# qfp160_socket.net
KiCad netlist of a schematic drawn in EAGLE
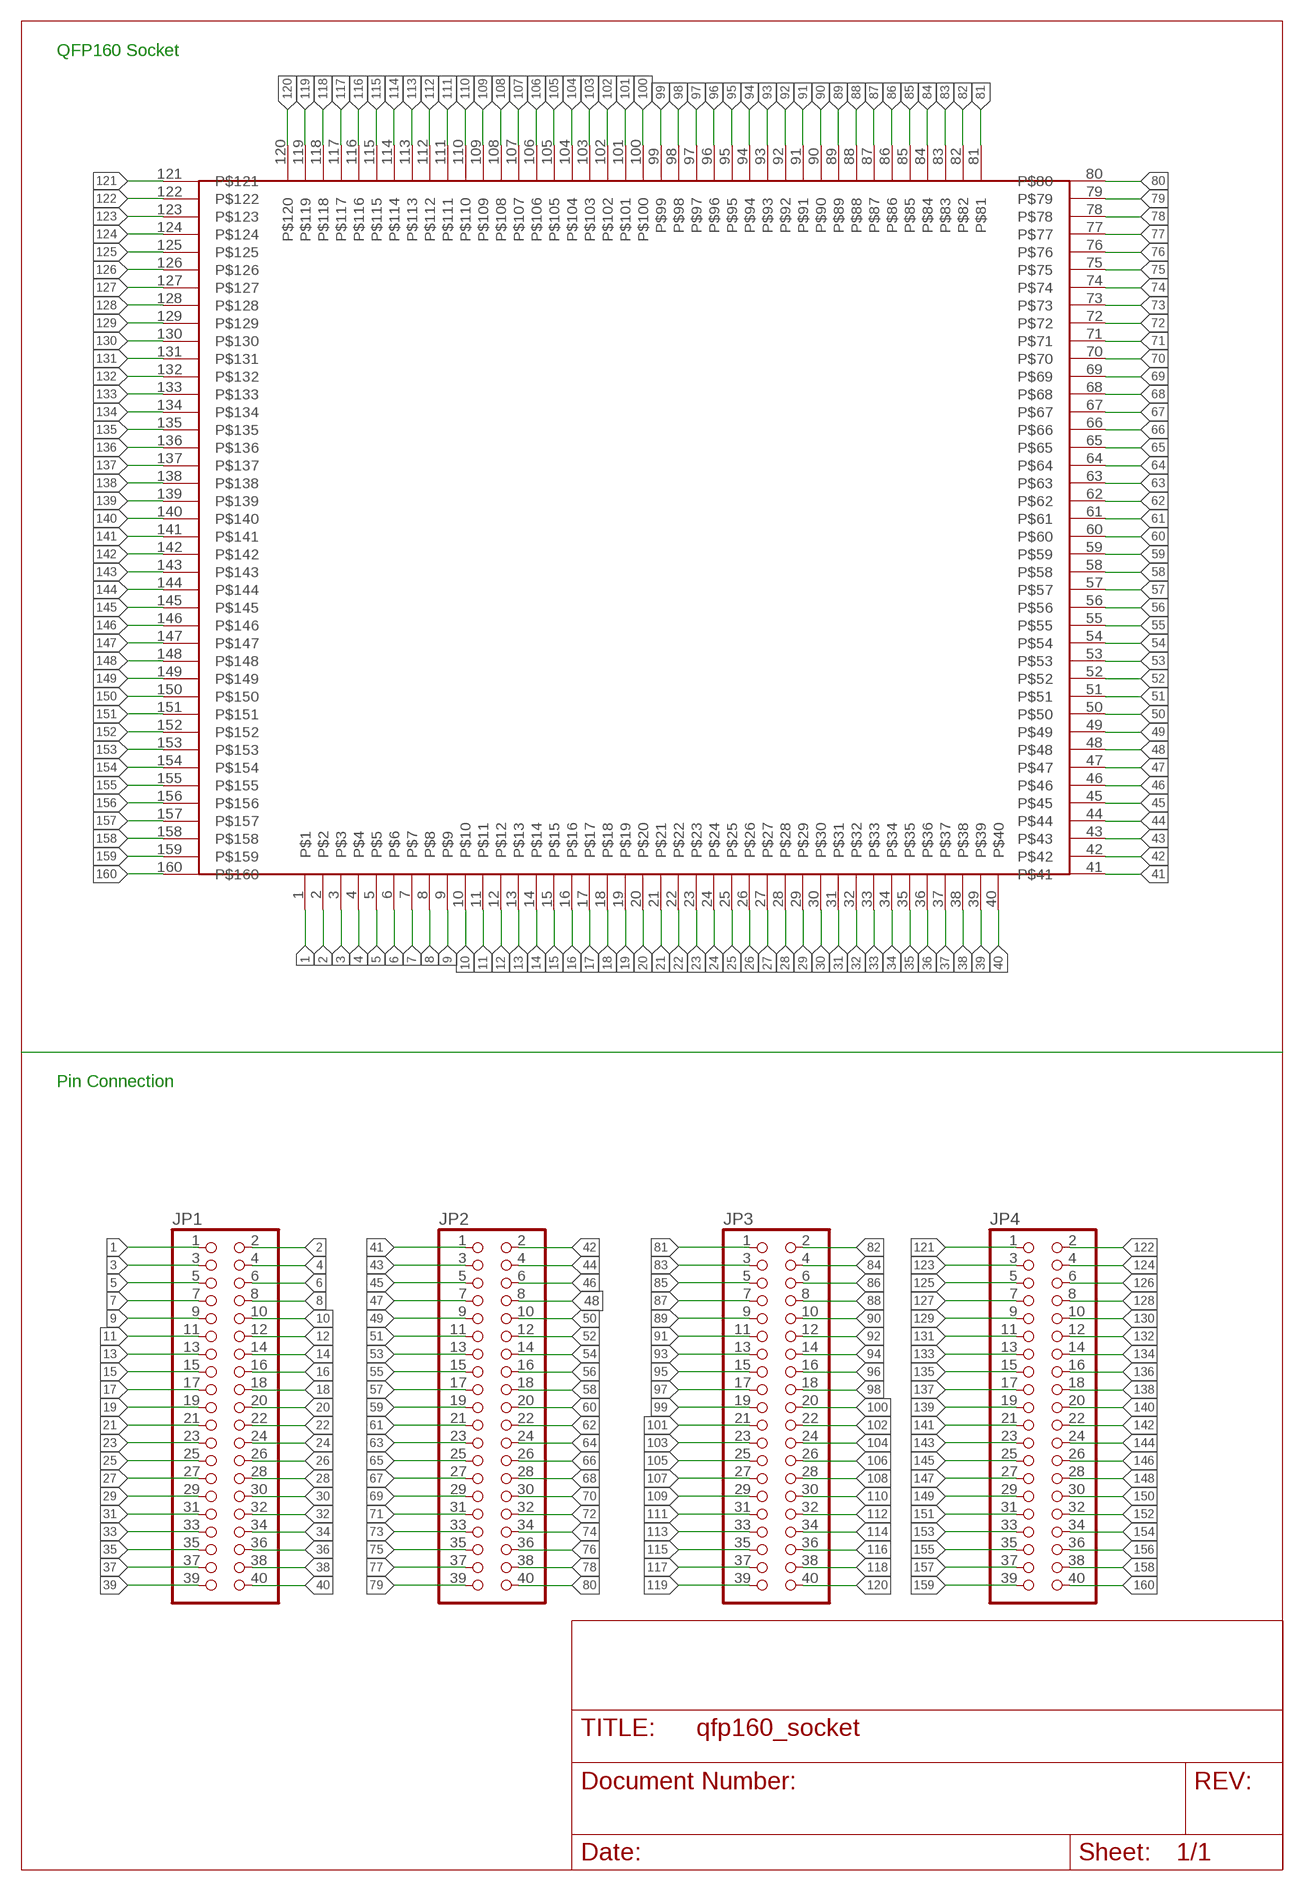
[diagram p0: schematic, sheet 1]

(export (version "E")
  (design (tool "Eeschema 10.0.6"))
  (components
    (comp (ref "JP1")
      (value "PINHD-2X20")
      (footprint "eagle-import:2X20")
      (libsource (lib "eagle-import") (part "PINHD-2X20"))
    )
    (comp (ref "JP2")
      (value "PINHD-2X20")
      (footprint "eagle-import:2X20")
      (libsource (lib "eagle-import") (part "PINHD-2X20"))
    )
    (comp (ref "JP3")
      (value "PINHD-2X20")
      (footprint "eagle-import:2X20")
      (libsource (lib "eagle-import") (part "PINHD-2X20"))
    )
    (comp (ref "JP4")
      (value "PINHD-2X20")
      (footprint "eagle-import:2X20")
      (libsource (lib "eagle-import") (part "PINHD-2X20"))
    )
    (comp (ref "U$1")
      (value "QFP160_SOCKET")
      (footprint "eagle-import:QFP160_SOCKET")
      (libsource (lib "eagle-import") (part "QFP160_SOCKET"))
    )
  )
  (nets
    (net (code "1") (name "1") (class "Default")
      (node (ref "JP1") (pin "1") (pinfunction "1_1") (pintype "passive"))
      (node (ref "U$1") (pin "1") (pinfunction "P$1_1") (pintype "bidirectional"))
    )
    (net (code "2") (name "2") (class "Default")
      (node (ref "JP1") (pin "2") (pinfunction "2_2") (pintype "passive"))
      (node (ref "U$1") (pin "2") (pinfunction "P$2_2") (pintype "bidirectional"))
    )
    (net (code "3") (name "3") (class "Default")
      (node (ref "JP1") (pin "3") (pinfunction "3_3") (pintype "passive"))
      (node (ref "U$1") (pin "3") (pinfunction "P$3_3") (pintype "bidirectional"))
    )
    (net (code "4") (name "4") (class "Default")
      (node (ref "JP1") (pin "4") (pinfunction "4_4") (pintype "passive"))
      (node (ref "U$1") (pin "4") (pinfunction "P$4_4") (pintype "bidirectional"))
    )
    (net (code "5") (name "5") (class "Default")
      (node (ref "JP1") (pin "5") (pinfunction "5_5") (pintype "passive"))
      (node (ref "U$1") (pin "5") (pinfunction "P$5_5") (pintype "bidirectional"))
    )
    (net (code "6") (name "6") (class "Default")
      (node (ref "JP1") (pin "6") (pinfunction "6_6") (pintype "passive"))
      (node (ref "U$1") (pin "6") (pinfunction "P$6_6") (pintype "bidirectional"))
    )
    (net (code "7") (name "7") (class "Default")
      (node (ref "JP1") (pin "7") (pinfunction "7_7") (pintype "passive"))
      (node (ref "U$1") (pin "7") (pinfunction "P$7_7") (pintype "bidirectional"))
    )
    (net (code "8") (name "8") (class "Default")
      (node (ref "JP1") (pin "8") (pinfunction "8_8") (pintype "passive"))
      (node (ref "U$1") (pin "8") (pinfunction "P$8_8") (pintype "bidirectional"))
    )
    (net (code "9") (name "9") (class "Default")
      (node (ref "JP1") (pin "9") (pinfunction "9_9") (pintype "passive"))
      (node (ref "U$1") (pin "9") (pinfunction "P$9_9") (pintype "bidirectional"))
    )
    (net (code "10") (name "10") (class "Default")
      (node (ref "JP1") (pin "10") (pinfunction "10_10") (pintype "passive"))
      (node (ref "U$1") (pin "10") (pinfunction "P$10_10") (pintype "bidirectional"))
    )
    (net (code "11") (name "11") (class "Default")
      (node (ref "JP1") (pin "11") (pinfunction "11_11") (pintype "passive"))
      (node (ref "U$1") (pin "11") (pinfunction "P$11_11") (pintype "bidirectional"))
    )
    (net (code "12") (name "12") (class "Default")
      (node (ref "JP1") (pin "12") (pinfunction "12_12") (pintype "passive"))
      (node (ref "U$1") (pin "12") (pinfunction "P$12_12") (pintype "bidirectional"))
    )
    (net (code "13") (name "13") (class "Default")
      (node (ref "JP1") (pin "13") (pinfunction "13_13") (pintype "passive"))
      (node (ref "U$1") (pin "13") (pinfunction "P$13_13") (pintype "bidirectional"))
    )
    (net (code "14") (name "14") (class "Default")
      (node (ref "JP1") (pin "14") (pinfunction "14_14") (pintype "passive"))
      (node (ref "U$1") (pin "14") (pinfunction "P$14_14") (pintype "bidirectional"))
    )
    (net (code "15") (name "15") (class "Default")
      (node (ref "JP1") (pin "15") (pinfunction "15_15") (pintype "passive"))
      (node (ref "U$1") (pin "15") (pinfunction "P$15_15") (pintype "bidirectional"))
    )
    (net (code "16") (name "16") (class "Default")
      (node (ref "JP1") (pin "16") (pinfunction "16_16") (pintype "passive"))
      (node (ref "U$1") (pin "16") (pinfunction "P$16_16") (pintype "bidirectional"))
    )
    (net (code "17") (name "17") (class "Default")
      (node (ref "JP1") (pin "17") (pinfunction "17_17") (pintype "passive"))
      (node (ref "U$1") (pin "17") (pinfunction "P$17_17") (pintype "bidirectional"))
    )
    (net (code "18") (name "18") (class "Default")
      (node (ref "JP1") (pin "18") (pinfunction "18_18") (pintype "passive"))
      (node (ref "U$1") (pin "18") (pinfunction "P$18_18") (pintype "bidirectional"))
    )
    (net (code "19") (name "19") (class "Default")
      (node (ref "JP1") (pin "19") (pinfunction "19_19") (pintype "passive"))
      (node (ref "U$1") (pin "19") (pinfunction "P$19_19") (pintype "bidirectional"))
    )
    (net (code "20") (name "20") (class "Default")
      (node (ref "JP1") (pin "20") (pinfunction "20_20") (pintype "passive"))
      (node (ref "U$1") (pin "20") (pinfunction "P$20_20") (pintype "bidirectional"))
    )
    (net (code "21") (name "21") (class "Default")
      (node (ref "JP1") (pin "21") (pinfunction "21_21") (pintype "passive"))
      (node (ref "U$1") (pin "21") (pinfunction "P$21_21") (pintype "bidirectional"))
    )
    (net (code "22") (name "22") (class "Default")
      (node (ref "JP1") (pin "22") (pinfunction "22_22") (pintype "passive"))
      (node (ref "U$1") (pin "22") (pinfunction "P$22_22") (pintype "bidirectional"))
    )
    (net (code "23") (name "23") (class "Default")
      (node (ref "JP1") (pin "23") (pinfunction "23_23") (pintype "passive"))
      (node (ref "U$1") (pin "23") (pinfunction "P$23_23") (pintype "bidirectional"))
    )
    (net (code "24") (name "24") (class "Default")
      (node (ref "JP1") (pin "24") (pinfunction "24_24") (pintype "passive"))
      (node (ref "U$1") (pin "24") (pinfunction "P$24_24") (pintype "bidirectional"))
    )
    (net (code "25") (name "25") (class "Default")
      (node (ref "JP1") (pin "25") (pinfunction "25_25") (pintype "passive"))
      (node (ref "U$1") (pin "25") (pinfunction "P$25_25") (pintype "bidirectional"))
    )
    (net (code "26") (name "26") (class "Default")
      (node (ref "JP1") (pin "26") (pinfunction "26_26") (pintype "passive"))
      (node (ref "U$1") (pin "26") (pinfunction "P$26_26") (pintype "bidirectional"))
    )
    (net (code "27") (name "27") (class "Default")
      (node (ref "JP1") (pin "27") (pinfunction "27_27") (pintype "passive"))
      (node (ref "U$1") (pin "27") (pinfunction "P$27_27") (pintype "bidirectional"))
    )
    (net (code "28") (name "28") (class "Default")
      (node (ref "JP1") (pin "28") (pinfunction "28_28") (pintype "passive"))
      (node (ref "U$1") (pin "28") (pinfunction "P$28_28") (pintype "bidirectional"))
    )
    (net (code "29") (name "29") (class "Default")
      (node (ref "JP1") (pin "29") (pinfunction "29_29") (pintype "passive"))
      (node (ref "U$1") (pin "29") (pinfunction "P$29_29") (pintype "bidirectional"))
    )
    (net (code "30") (name "30") (class "Default")
      (node (ref "JP1") (pin "30") (pinfunction "30_30") (pintype "passive"))
      (node (ref "U$1") (pin "30") (pinfunction "P$30_30") (pintype "bidirectional"))
    )
    (net (code "31") (name "31") (class "Default")
      (node (ref "JP1") (pin "31") (pinfunction "31_31") (pintype "passive"))
      (node (ref "U$1") (pin "31") (pinfunction "P$31_31") (pintype "bidirectional"))
    )
    (net (code "32") (name "32") (class "Default")
      (node (ref "JP1") (pin "32") (pinfunction "32_32") (pintype "passive"))
      (node (ref "U$1") (pin "32") (pinfunction "P$32_32") (pintype "bidirectional"))
    )
    (net (code "33") (name "33") (class "Default")
      (node (ref "JP1") (pin "33") (pinfunction "33_33") (pintype "passive"))
      (node (ref "U$1") (pin "33") (pinfunction "P$33_33") (pintype "bidirectional"))
    )
    (net (code "34") (name "34") (class "Default")
      (node (ref "JP1") (pin "34") (pinfunction "34_34") (pintype "passive"))
      (node (ref "U$1") (pin "34") (pinfunction "P$34_34") (pintype "bidirectional"))
    )
    (net (code "35") (name "35") (class "Default")
      (node (ref "JP1") (pin "35") (pinfunction "35_35") (pintype "passive"))
      (node (ref "U$1") (pin "35") (pinfunction "P$35_35") (pintype "bidirectional"))
    )
    (net (code "36") (name "36") (class "Default")
      (node (ref "JP1") (pin "36") (pinfunction "36_36") (pintype "passive"))
      (node (ref "U$1") (pin "36") (pinfunction "P$36_36") (pintype "bidirectional"))
    )
    (net (code "37") (name "37") (class "Default")
      (node (ref "JP1") (pin "37") (pinfunction "37_37") (pintype "passive"))
      (node (ref "U$1") (pin "37") (pinfunction "P$37_37") (pintype "bidirectional"))
    )
    (net (code "38") (name "38") (class "Default")
      (node (ref "JP1") (pin "38") (pinfunction "38_38") (pintype "passive"))
      (node (ref "U$1") (pin "38") (pinfunction "P$38_38") (pintype "bidirectional"))
    )
    (net (code "39") (name "39") (class "Default")
      (node (ref "JP1") (pin "39") (pinfunction "39_39") (pintype "passive"))
      (node (ref "U$1") (pin "39") (pinfunction "P$39_39") (pintype "bidirectional"))
    )
    (net (code "40") (name "40") (class "Default")
      (node (ref "JP1") (pin "40") (pinfunction "40_40") (pintype "passive"))
      (node (ref "U$1") (pin "40") (pinfunction "P$40_40") (pintype "bidirectional"))
    )
    (net (code "41") (name "41") (class "Default")
      (node (ref "JP2") (pin "1") (pinfunction "1_1") (pintype "passive"))
      (node (ref "U$1") (pin "41") (pinfunction "P$41_41") (pintype "bidirectional"))
    )
    (net (code "42") (name "42") (class "Default")
      (node (ref "JP2") (pin "2") (pinfunction "2_2") (pintype "passive"))
      (node (ref "U$1") (pin "42") (pinfunction "P$42_42") (pintype "bidirectional"))
    )
    (net (code "43") (name "43") (class "Default")
      (node (ref "JP2") (pin "3") (pinfunction "3_3") (pintype "passive"))
      (node (ref "U$1") (pin "43") (pinfunction "P$43_43") (pintype "bidirectional"))
    )
    (net (code "44") (name "44") (class "Default")
      (node (ref "JP2") (pin "4") (pinfunction "4_4") (pintype "passive"))
      (node (ref "U$1") (pin "44") (pinfunction "P$44_44") (pintype "bidirectional"))
    )
    (net (code "45") (name "45") (class "Default")
      (node (ref "JP2") (pin "5") (pinfunction "5_5") (pintype "passive"))
      (node (ref "U$1") (pin "45") (pinfunction "P$45_45") (pintype "bidirectional"))
    )
    (net (code "46") (name "46") (class "Default")
      (node (ref "JP2") (pin "6") (pinfunction "6_6") (pintype "passive"))
      (node (ref "U$1") (pin "46") (pinfunction "P$46_46") (pintype "bidirectional"))
    )
    (net (code "47") (name "47") (class "Default")
      (node (ref "JP2") (pin "7") (pinfunction "7_7") (pintype "passive"))
      (node (ref "U$1") (pin "47") (pinfunction "P$47_47") (pintype "bidirectional"))
    )
    (net (code "48") (name "48") (class "Default")
      (node (ref "JP2") (pin "8") (pinfunction "8_8") (pintype "passive"))
      (node (ref "U$1") (pin "48") (pinfunction "P$48_48") (pintype "bidirectional"))
    )
    (net (code "49") (name "49") (class "Default")
      (node (ref "JP2") (pin "9") (pinfunction "9_9") (pintype "passive"))
      (node (ref "U$1") (pin "49") (pinfunction "P$49_49") (pintype "bidirectional"))
    )
    (net (code "50") (name "50") (class "Default")
      (node (ref "JP2") (pin "10") (pinfunction "10_10") (pintype "passive"))
      (node (ref "U$1") (pin "50") (pinfunction "P$50_50") (pintype "bidirectional"))
    )
    (net (code "51") (name "51") (class "Default")
      (node (ref "JP2") (pin "11") (pinfunction "11_11") (pintype "passive"))
      (node (ref "U$1") (pin "51") (pinfunction "P$51_51") (pintype "bidirectional"))
    )
    (net (code "52") (name "52") (class "Default")
      (node (ref "JP2") (pin "12") (pinfunction "12_12") (pintype "passive"))
      (node (ref "U$1") (pin "52") (pinfunction "P$52_52") (pintype "bidirectional"))
    )
    (net (code "53") (name "53") (class "Default")
      (node (ref "JP2") (pin "13") (pinfunction "13_13") (pintype "passive"))
      (node (ref "U$1") (pin "53") (pinfunction "P$53_53") (pintype "bidirectional"))
    )
    (net (code "54") (name "54") (class "Default")
      (node (ref "JP2") (pin "14") (pinfunction "14_14") (pintype "passive"))
      (node (ref "U$1") (pin "54") (pinfunction "P$54_54") (pintype "bidirectional"))
    )
    (net (code "55") (name "55") (class "Default")
      (node (ref "JP2") (pin "15") (pinfunction "15_15") (pintype "passive"))
      (node (ref "U$1") (pin "55") (pinfunction "P$55_55") (pintype "bidirectional"))
    )
    (net (code "56") (name "56") (class "Default")
      (node (ref "JP2") (pin "16") (pinfunction "16_16") (pintype "passive"))
      (node (ref "U$1") (pin "56") (pinfunction "P$56_56") (pintype "bidirectional"))
    )
    (net (code "57") (name "57") (class "Default")
      (node (ref "JP2") (pin "17") (pinfunction "17_17") (pintype "passive"))
      (node (ref "U$1") (pin "57") (pinfunction "P$57_57") (pintype "bidirectional"))
    )
    (net (code "58") (name "58") (class "Default")
      (node (ref "JP2") (pin "18") (pinfunction "18_18") (pintype "passive"))
      (node (ref "U$1") (pin "58") (pinfunction "P$58_58") (pintype "bidirectional"))
    )
    (net (code "59") (name "59") (class "Default")
      (node (ref "JP2") (pin "19") (pinfunction "19_19") (pintype "passive"))
      (node (ref "U$1") (pin "59") (pinfunction "P$59_59") (pintype "bidirectional"))
    )
    (net (code "60") (name "60") (class "Default")
      (node (ref "JP2") (pin "20") (pinfunction "20_20") (pintype "passive"))
      (node (ref "U$1") (pin "60") (pinfunction "P$60_60") (pintype "bidirectional"))
    )
    (net (code "61") (name "61") (class "Default")
      (node (ref "JP2") (pin "21") (pinfunction "21_21") (pintype "passive"))
      (node (ref "U$1") (pin "61") (pinfunction "P$61_61") (pintype "bidirectional"))
    )
    (net (code "62") (name "62") (class "Default")
      (node (ref "JP2") (pin "22") (pinfunction "22_22") (pintype "passive"))
      (node (ref "U$1") (pin "62") (pinfunction "P$62_62") (pintype "bidirectional"))
    )
    (net (code "63") (name "63") (class "Default")
      (node (ref "JP2") (pin "23") (pinfunction "23_23") (pintype "passive"))
      (node (ref "U$1") (pin "63") (pinfunction "P$63_63") (pintype "bidirectional"))
    )
    (net (code "64") (name "64") (class "Default")
      (node (ref "JP2") (pin "24") (pinfunction "24_24") (pintype "passive"))
      (node (ref "U$1") (pin "64") (pinfunction "P$64_64") (pintype "bidirectional"))
    )
    (net (code "65") (name "65") (class "Default")
      (node (ref "JP2") (pin "25") (pinfunction "25_25") (pintype "passive"))
      (node (ref "U$1") (pin "65") (pinfunction "P$65_65") (pintype "bidirectional"))
    )
    (net (code "66") (name "66") (class "Default")
      (node (ref "JP2") (pin "26") (pinfunction "26_26") (pintype "passive"))
      (node (ref "U$1") (pin "66") (pinfunction "P$66_66") (pintype "bidirectional"))
    )
    (net (code "67") (name "67") (class "Default")
      (node (ref "JP2") (pin "27") (pinfunction "27_27") (pintype "passive"))
      (node (ref "U$1") (pin "67") (pinfunction "P$67_67") (pintype "bidirectional"))
    )
    (net (code "68") (name "68") (class "Default")
      (node (ref "JP2") (pin "28") (pinfunction "28_28") (pintype "passive"))
      (node (ref "U$1") (pin "68") (pinfunction "P$68_68") (pintype "bidirectional"))
    )
    (net (code "69") (name "69") (class "Default")
      (node (ref "JP2") (pin "29") (pinfunction "29_29") (pintype "passive"))
      (node (ref "U$1") (pin "69") (pinfunction "P$69_69") (pintype "bidirectional"))
    )
    (net (code "70") (name "70") (class "Default")
      (node (ref "JP2") (pin "30") (pinfunction "30_30") (pintype "passive"))
      (node (ref "U$1") (pin "70") (pinfunction "P$70_70") (pintype "bidirectional"))
    )
    (net (code "71") (name "71") (class "Default")
      (node (ref "JP2") (pin "31") (pinfunction "31_31") (pintype "passive"))
      (node (ref "U$1") (pin "71") (pinfunction "P$71_71") (pintype "bidirectional"))
    )
    (net (code "72") (name "72") (class "Default")
      (node (ref "JP2") (pin "32") (pinfunction "32_32") (pintype "passive"))
      (node (ref "U$1") (pin "72") (pinfunction "P$72_72") (pintype "bidirectional"))
    )
    (net (code "73") (name "73") (class "Default")
      (node (ref "JP2") (pin "33") (pinfunction "33_33") (pintype "passive"))
      (node (ref "U$1") (pin "73") (pinfunction "P$73_73") (pintype "bidirectional"))
    )
    (net (code "74") (name "74") (class "Default")
      (node (ref "JP2") (pin "34") (pinfunction "34_34") (pintype "passive"))
      (node (ref "U$1") (pin "74") (pinfunction "P$74_74") (pintype "bidirectional"))
    )
    (net (code "75") (name "75") (class "Default")
      (node (ref "JP2") (pin "35") (pinfunction "35_35") (pintype "passive"))
      (node (ref "U$1") (pin "75") (pinfunction "P$75_75") (pintype "bidirectional"))
    )
    (net (code "76") (name "76") (class "Default")
      (node (ref "JP2") (pin "36") (pinfunction "36_36") (pintype "passive"))
      (node (ref "U$1") (pin "76") (pinfunction "P$76_76") (pintype "bidirectional"))
    )
    (net (code "77") (name "77") (class "Default")
      (node (ref "JP2") (pin "37") (pinfunction "37_37") (pintype "passive"))
      (node (ref "U$1") (pin "77") (pinfunction "P$77_77") (pintype "bidirectional"))
    )
    (net (code "78") (name "78") (class "Default")
      (node (ref "JP2") (pin "38") (pinfunction "38_38") (pintype "passive"))
      (node (ref "U$1") (pin "78") (pinfunction "P$78_78") (pintype "bidirectional"))
    )
    (net (code "79") (name "79") (class "Default")
      (node (ref "JP2") (pin "39") (pinfunction "39_39") (pintype "passive"))
      (node (ref "U$1") (pin "79") (pinfunction "P$79_79") (pintype "bidirectional"))
    )
    (net (code "80") (name "80") (class "Default")
      (node (ref "JP2") (pin "40") (pinfunction "40_40") (pintype "passive"))
      (node (ref "U$1") (pin "80") (pinfunction "P$80_80") (pintype "bidirectional"))
    )
    (net (code "81") (name "81") (class "Default")
      (node (ref "JP3") (pin "1") (pinfunction "1_1") (pintype "passive"))
      (node (ref "U$1") (pin "81") (pinfunction "P$81_81") (pintype "bidirectional"))
    )
    (net (code "82") (name "82") (class "Default")
      (node (ref "JP3") (pin "2") (pinfunction "2_2") (pintype "passive"))
      (node (ref "U$1") (pin "82") (pinfunction "P$82_82") (pintype "bidirectional"))
    )
    (net (code "83") (name "83") (class "Default")
      (node (ref "JP3") (pin "3") (pinfunction "3_3") (pintype "passive"))
      (node (ref "U$1") (pin "83") (pinfunction "P$83_83") (pintype "bidirectional"))
    )
    (net (code "84") (name "84") (class "Default")
      (node (ref "JP3") (pin "4") (pinfunction "4_4") (pintype "passive"))
      (node (ref "U$1") (pin "84") (pinfunction "P$84_84") (pintype "bidirectional"))
    )
    (net (code "85") (name "85") (class "Default")
      (node (ref "JP3") (pin "5") (pinfunction "5_5") (pintype "passive"))
      (node (ref "U$1") (pin "85") (pinfunction "P$85_85") (pintype "bidirectional"))
    )
    (net (code "86") (name "86") (class "Default")
      (node (ref "JP3") (pin "6") (pinfunction "6_6") (pintype "passive"))
      (node (ref "U$1") (pin "86") (pinfunction "P$86_86") (pintype "bidirectional"))
    )
    (net (code "87") (name "87") (class "Default")
      (node (ref "JP3") (pin "7") (pinfunction "7_7") (pintype "passive"))
      (node (ref "U$1") (pin "87") (pinfunction "P$87_87") (pintype "bidirectional"))
    )
    (net (code "88") (name "88") (class "Default")
      (node (ref "JP3") (pin "8") (pinfunction "8_8") (pintype "passive"))
      (node (ref "U$1") (pin "88") (pinfunction "P$88_88") (pintype "bidirectional"))
    )
    (net (code "89") (name "89") (class "Default")
      (node (ref "JP3") (pin "9") (pinfunction "9_9") (pintype "passive"))
      (node (ref "U$1") (pin "89") (pinfunction "P$89_89") (pintype "bidirectional"))
    )
    (net (code "90") (name "90") (class "Default")
      (node (ref "JP3") (pin "10") (pinfunction "10_10") (pintype "passive"))
      (node (ref "U$1") (pin "90") (pinfunction "P$90_90") (pintype "bidirectional"))
    )
    (net (code "91") (name "91") (class "Default")
      (node (ref "JP3") (pin "11") (pinfunction "11_11") (pintype "passive"))
      (node (ref "U$1") (pin "91") (pinfunction "P$91_91") (pintype "bidirectional"))
    )
    (net (code "92") (name "92") (class "Default")
      (node (ref "JP3") (pin "12") (pinfunction "12_12") (pintype "passive"))
      (node (ref "U$1") (pin "92") (pinfunction "P$92_92") (pintype "bidirectional"))
    )
    (net (code "93") (name "93") (class "Default")
      (node (ref "JP3") (pin "13") (pinfunction "13_13") (pintype "passive"))
      (node (ref "U$1") (pin "93") (pinfunction "P$93_93") (pintype "bidirectional"))
    )
    (net (code "94") (name "94") (class "Default")
      (node (ref "JP3") (pin "14") (pinfunction "14_14") (pintype "passive"))
      (node (ref "U$1") (pin "94") (pinfunction "P$94_94") (pintype "bidirectional"))
    )
    (net (code "95") (name "95") (class "Default")
      (node (ref "JP3") (pin "15") (pinfunction "15_15") (pintype "passive"))
      (node (ref "U$1") (pin "95") (pinfunction "P$95_95") (pintype "bidirectional"))
    )
    (net (code "96") (name "96") (class "Default")
      (node (ref "JP3") (pin "16") (pinfunction "16_16") (pintype "passive"))
      (node (ref "U$1") (pin "96") (pinfunction "P$96_96") (pintype "bidirectional"))
    )
    (net (code "97") (name "97") (class "Default")
      (node (ref "JP3") (pin "17") (pinfunction "17_17") (pintype "passive"))
      (node (ref "U$1") (pin "97") (pinfunction "P$97_97") (pintype "bidirectional"))
    )
    (net (code "98") (name "98") (class "Default")
      (node (ref "JP3") (pin "18") (pinfunction "18_18") (pintype "passive"))
      (node (ref "U$1") (pin "98") (pinfunction "P$98_98") (pintype "bidirectional"))
    )
    (net (code "99") (name "99") (class "Default")
      (node (ref "JP3") (pin "19") (pinfunction "19_19") (pintype "passive"))
      (node (ref "U$1") (pin "99") (pinfunction "P$99_99") (pintype "bidirectional"))
    )
    (net (code "100") (name "100") (class "Default")
      (node (ref "JP3") (pin "20") (pinfunction "20_20") (pintype "passive"))
      (node (ref "U$1") (pin "100") (pinfunction "P$100_100") (pintype "bidirectional"))
    )
    (net (code "101") (name "101") (class "Default")
      (node (ref "JP3") (pin "21") (pinfunction "21_21") (pintype "passive"))
      (node (ref "U$1") (pin "101") (pinfunction "P$101_101") (pintype "bidirectional"))
    )
    (net (code "102") (name "102") (class "Default")
      (node (ref "JP3") (pin "22") (pinfunction "22_22") (pintype "passive"))
      (node (ref "U$1") (pin "102") (pinfunction "P$102_102") (pintype "bidirectional"))
    )
    (net (code "103") (name "103") (class "Default")
      (node (ref "JP3") (pin "23") (pinfunction "23_23") (pintype "passive"))
      (node (ref "U$1") (pin "103") (pinfunction "P$103_103") (pintype "bidirectional"))
    )
    (net (code "104") (name "104") (class "Default")
      (node (ref "JP3") (pin "24") (pinfunction "24_24") (pintype "passive"))
      (node (ref "U$1") (pin "104") (pinfunction "P$104_104") (pintype "bidirectional"))
    )
    (net (code "105") (name "105") (class "Default")
      (node (ref "JP3") (pin "25") (pinfunction "25_25") (pintype "passive"))
      (node (ref "U$1") (pin "105") (pinfunction "P$105_105") (pintype "bidirectional"))
    )
    (net (code "106") (name "106") (class "Default")
      (node (ref "JP3") (pin "26") (pinfunction "26_26") (pintype "passive"))
      (node (ref "U$1") (pin "106") (pinfunction "P$106_106") (pintype "bidirectional"))
    )
    (net (code "107") (name "107") (class "Default")
      (node (ref "JP3") (pin "27") (pinfunction "27_27") (pintype "passive"))
      (node (ref "U$1") (pin "107") (pinfunction "P$107_107") (pintype "bidirectional"))
    )
    (net (code "108") (name "108") (class "Default")
      (node (ref "JP3") (pin "28") (pinfunction "28_28") (pintype "passive"))
      (node (ref "U$1") (pin "108") (pinfunction "P$108_108") (pintype "bidirectional"))
    )
    (net (code "109") (name "109") (class "Default")
      (node (ref "JP3") (pin "29") (pinfunction "29_29") (pintype "passive"))
      (node (ref "U$1") (pin "109") (pinfunction "P$109_109") (pintype "bidirectional"))
    )
    (net (code "110") (name "110") (class "Default")
      (node (ref "JP3") (pin "30") (pinfunction "30_30") (pintype "passive"))
      (node (ref "U$1") (pin "110") (pinfunction "P$110_110") (pintype "bidirectional"))
    )
    (net (code "111") (name "111") (class "Default")
      (node (ref "JP3") (pin "31") (pinfunction "31_31") (pintype "passive"))
      (node (ref "U$1") (pin "111") (pinfunction "P$111_111") (pintype "bidirectional"))
    )
    (net (code "112") (name "112") (class "Default")
      (node (ref "JP3") (pin "32") (pinfunction "32_32") (pintype "passive"))
      (node (ref "U$1") (pin "112") (pinfunction "P$112_112") (pintype "bidirectional"))
    )
    (net (code "113") (name "113") (class "Default")
      (node (ref "JP3") (pin "33") (pinfunction "33_33") (pintype "passive"))
      (node (ref "U$1") (pin "113") (pinfunction "P$113_113") (pintype "bidirectional"))
    )
    (net (code "114") (name "114") (class "Default")
      (node (ref "JP3") (pin "34") (pinfunction "34_34") (pintype "passive"))
      (node (ref "U$1") (pin "114") (pinfunction "P$114_114") (pintype "bidirectional"))
    )
    (net (code "115") (name "115") (class "Default")
      (node (ref "JP3") (pin "35") (pinfunction "35_35") (pintype "passive"))
      (node (ref "U$1") (pin "115") (pinfunction "P$115_115") (pintype "bidirectional"))
    )
    (net (code "116") (name "116") (class "Default")
      (node (ref "JP3") (pin "36") (pinfunction "36_36") (pintype "passive"))
      (node (ref "U$1") (pin "116") (pinfunction "P$116_116") (pintype "bidirectional"))
    )
    (net (code "117") (name "117") (class "Default")
      (node (ref "JP3") (pin "37") (pinfunction "37_37") (pintype "passive"))
      (node (ref "U$1") (pin "117") (pinfunction "P$117_117") (pintype "bidirectional"))
    )
    (net (code "118") (name "118") (class "Default")
      (node (ref "JP3") (pin "38") (pinfunction "38_38") (pintype "passive"))
      (node (ref "U$1") (pin "118") (pinfunction "P$118_118") (pintype "bidirectional"))
    )
    (net (code "119") (name "119") (class "Default")
      (node (ref "JP3") (pin "39") (pinfunction "39_39") (pintype "passive"))
      (node (ref "U$1") (pin "119") (pinfunction "P$119_119") (pintype "bidirectional"))
    )
    (net (code "120") (name "120") (class "Default")
      (node (ref "JP3") (pin "40") (pinfunction "40_40") (pintype "passive"))
      (node (ref "U$1") (pin "120") (pinfunction "P$120_120") (pintype "bidirectional"))
    )
    (net (code "121") (name "121") (class "Default")
      (node (ref "JP4") (pin "1") (pinfunction "1_1") (pintype "passive"))
      (node (ref "U$1") (pin "121") (pinfunction "P$121_121") (pintype "bidirectional"))
    )
    (net (code "122") (name "122") (class "Default")
      (node (ref "JP4") (pin "2") (pinfunction "2_2") (pintype "passive"))
      (node (ref "U$1") (pin "122") (pinfunction "P$122_122") (pintype "bidirectional"))
    )
    (net (code "123") (name "123") (class "Default")
      (node (ref "JP4") (pin "3") (pinfunction "3_3") (pintype "passive"))
      (node (ref "U$1") (pin "123") (pinfunction "P$123_123") (pintype "bidirectional"))
    )
    (net (code "124") (name "124") (class "Default")
      (node (ref "JP4") (pin "4") (pinfunction "4_4") (pintype "passive"))
      (node (ref "U$1") (pin "124") (pinfunction "P$124_124") (pintype "bidirectional"))
    )
    (net (code "125") (name "125") (class "Default")
      (node (ref "JP4") (pin "5") (pinfunction "5_5") (pintype "passive"))
      (node (ref "U$1") (pin "125") (pinfunction "P$125_125") (pintype "bidirectional"))
    )
    (net (code "126") (name "126") (class "Default")
      (node (ref "JP4") (pin "6") (pinfunction "6_6") (pintype "passive"))
      (node (ref "U$1") (pin "126") (pinfunction "P$126_126") (pintype "bidirectional"))
    )
    (net (code "127") (name "127") (class "Default")
      (node (ref "JP4") (pin "7") (pinfunction "7_7") (pintype "passive"))
      (node (ref "U$1") (pin "127") (pinfunction "P$127_127") (pintype "bidirectional"))
    )
    (net (code "128") (name "128") (class "Default")
      (node (ref "JP4") (pin "8") (pinfunction "8_8") (pintype "passive"))
      (node (ref "U$1") (pin "128") (pinfunction "P$128_128") (pintype "bidirectional"))
    )
    (net (code "129") (name "129") (class "Default")
      (node (ref "JP4") (pin "9") (pinfunction "9_9") (pintype "passive"))
      (node (ref "U$1") (pin "129") (pinfunction "P$129_129") (pintype "bidirectional"))
    )
    (net (code "130") (name "130") (class "Default")
      (node (ref "JP4") (pin "10") (pinfunction "10_10") (pintype "passive"))
      (node (ref "U$1") (pin "130") (pinfunction "P$130_130") (pintype "bidirectional"))
    )
    (net (code "131") (name "131") (class "Default")
      (node (ref "JP4") (pin "11") (pinfunction "11_11") (pintype "passive"))
      (node (ref "U$1") (pin "131") (pinfunction "P$131_131") (pintype "bidirectional"))
    )
    (net (code "132") (name "132") (class "Default")
      (node (ref "JP4") (pin "12") (pinfunction "12_12") (pintype "passive"))
      (node (ref "U$1") (pin "132") (pinfunction "P$132_132") (pintype "bidirectional"))
    )
    (net (code "133") (name "133") (class "Default")
      (node (ref "JP4") (pin "13") (pinfunction "13_13") (pintype "passive"))
      (node (ref "U$1") (pin "133") (pinfunction "P$133_133") (pintype "bidirectional"))
    )
    (net (code "134") (name "134") (class "Default")
      (node (ref "JP4") (pin "14") (pinfunction "14_14") (pintype "passive"))
      (node (ref "U$1") (pin "134") (pinfunction "P$134_134") (pintype "bidirectional"))
    )
    (net (code "135") (name "135") (class "Default")
      (node (ref "JP4") (pin "15") (pinfunction "15_15") (pintype "passive"))
      (node (ref "U$1") (pin "135") (pinfunction "P$135_135") (pintype "bidirectional"))
    )
    (net (code "136") (name "136") (class "Default")
      (node (ref "JP4") (pin "16") (pinfunction "16_16") (pintype "passive"))
      (node (ref "U$1") (pin "136") (pinfunction "P$136_136") (pintype "bidirectional"))
    )
    (net (code "137") (name "137") (class "Default")
      (node (ref "JP4") (pin "17") (pinfunction "17_17") (pintype "passive"))
      (node (ref "U$1") (pin "137") (pinfunction "P$137_137") (pintype "bidirectional"))
    )
    (net (code "138") (name "138") (class "Default")
      (node (ref "JP4") (pin "18") (pinfunction "18_18") (pintype "passive"))
      (node (ref "U$1") (pin "138") (pinfunction "P$138_138") (pintype "bidirectional"))
    )
    (net (code "139") (name "139") (class "Default")
      (node (ref "JP4") (pin "19") (pinfunction "19_19") (pintype "passive"))
      (node (ref "U$1") (pin "139") (pinfunction "P$139_139") (pintype "bidirectional"))
    )
    (net (code "140") (name "140") (class "Default")
      (node (ref "JP4") (pin "20") (pinfunction "20_20") (pintype "passive"))
      (node (ref "U$1") (pin "140") (pinfunction "P$140_140") (pintype "bidirectional"))
    )
    (net (code "141") (name "141") (class "Default")
      (node (ref "JP4") (pin "21") (pinfunction "21_21") (pintype "passive"))
      (node (ref "U$1") (pin "141") (pinfunction "P$141_141") (pintype "bidirectional"))
    )
    (net (code "142") (name "142") (class "Default")
      (node (ref "JP4") (pin "22") (pinfunction "22_22") (pintype "passive"))
      (node (ref "U$1") (pin "142") (pinfunction "P$142_142") (pintype "bidirectional"))
    )
    (net (code "143") (name "143") (class "Default")
      (node (ref "JP4") (pin "23") (pinfunction "23_23") (pintype "passive"))
      (node (ref "U$1") (pin "143") (pinfunction "P$143_143") (pintype "bidirectional"))
    )
    (net (code "144") (name "144") (class "Default")
      (node (ref "JP4") (pin "24") (pinfunction "24_24") (pintype "passive"))
      (node (ref "U$1") (pin "144") (pinfunction "P$144_144") (pintype "bidirectional"))
    )
    (net (code "145") (name "145") (class "Default")
      (node (ref "JP4") (pin "25") (pinfunction "25_25") (pintype "passive"))
      (node (ref "U$1") (pin "145") (pinfunction "P$145_145") (pintype "bidirectional"))
    )
    (net (code "146") (name "146") (class "Default")
      (node (ref "JP4") (pin "26") (pinfunction "26_26") (pintype "passive"))
      (node (ref "U$1") (pin "146") (pinfunction "P$146_146") (pintype "bidirectional"))
    )
    (net (code "147") (name "147") (class "Default")
      (node (ref "JP4") (pin "27") (pinfunction "27_27") (pintype "passive"))
      (node (ref "U$1") (pin "147") (pinfunction "P$147_147") (pintype "bidirectional"))
    )
    (net (code "148") (name "148") (class "Default")
      (node (ref "JP4") (pin "28") (pinfunction "28_28") (pintype "passive"))
      (node (ref "U$1") (pin "148") (pinfunction "P$148_148") (pintype "bidirectional"))
    )
    (net (code "149") (name "149") (class "Default")
      (node (ref "JP4") (pin "29") (pinfunction "29_29") (pintype "passive"))
      (node (ref "U$1") (pin "149") (pinfunction "P$149_149") (pintype "bidirectional"))
    )
    (net (code "150") (name "150") (class "Default")
      (node (ref "JP4") (pin "30") (pinfunction "30_30") (pintype "passive"))
      (node (ref "U$1") (pin "150") (pinfunction "P$150_150") (pintype "bidirectional"))
    )
    (net (code "151") (name "151") (class "Default")
      (node (ref "JP4") (pin "31") (pinfunction "31_31") (pintype "passive"))
      (node (ref "U$1") (pin "151") (pinfunction "P$151_151") (pintype "bidirectional"))
    )
    (net (code "152") (name "152") (class "Default")
      (node (ref "JP4") (pin "32") (pinfunction "32_32") (pintype "passive"))
      (node (ref "U$1") (pin "152") (pinfunction "P$152_152") (pintype "bidirectional"))
    )
    (net (code "153") (name "153") (class "Default")
      (node (ref "JP4") (pin "33") (pinfunction "33_33") (pintype "passive"))
      (node (ref "U$1") (pin "153") (pinfunction "P$153_153") (pintype "bidirectional"))
    )
    (net (code "154") (name "154") (class "Default")
      (node (ref "JP4") (pin "34") (pinfunction "34_34") (pintype "passive"))
      (node (ref "U$1") (pin "154") (pinfunction "P$154_154") (pintype "bidirectional"))
    )
    (net (code "155") (name "155") (class "Default")
      (node (ref "JP4") (pin "35") (pinfunction "35_35") (pintype "passive"))
      (node (ref "U$1") (pin "155") (pinfunction "P$155_155") (pintype "bidirectional"))
    )
    (net (code "156") (name "156") (class "Default")
      (node (ref "JP4") (pin "36") (pinfunction "36_36") (pintype "passive"))
      (node (ref "U$1") (pin "156") (pinfunction "P$156_156") (pintype "bidirectional"))
    )
    (net (code "157") (name "157") (class "Default")
      (node (ref "JP4") (pin "37") (pinfunction "37_37") (pintype "passive"))
      (node (ref "U$1") (pin "157") (pinfunction "P$157_157") (pintype "bidirectional"))
    )
    (net (code "158") (name "158") (class "Default")
      (node (ref "JP4") (pin "38") (pinfunction "38_38") (pintype "passive"))
      (node (ref "U$1") (pin "158") (pinfunction "P$158_158") (pintype "bidirectional"))
    )
    (net (code "159") (name "159") (class "Default")
      (node (ref "JP4") (pin "39") (pinfunction "39_39") (pintype "passive"))
      (node (ref "U$1") (pin "159") (pinfunction "P$159_159") (pintype "bidirectional"))
    )
    (net (code "160") (name "160") (class "Default")
      (node (ref "JP4") (pin "40") (pinfunction "40_40") (pintype "passive"))
      (node (ref "U$1") (pin "160") (pinfunction "P$160_160") (pintype "bidirectional"))
    )
  )
)
